# SCH_meta-RCU_2025-01-19.net
KiCad netlist of a schematic drawn in EasyEDA
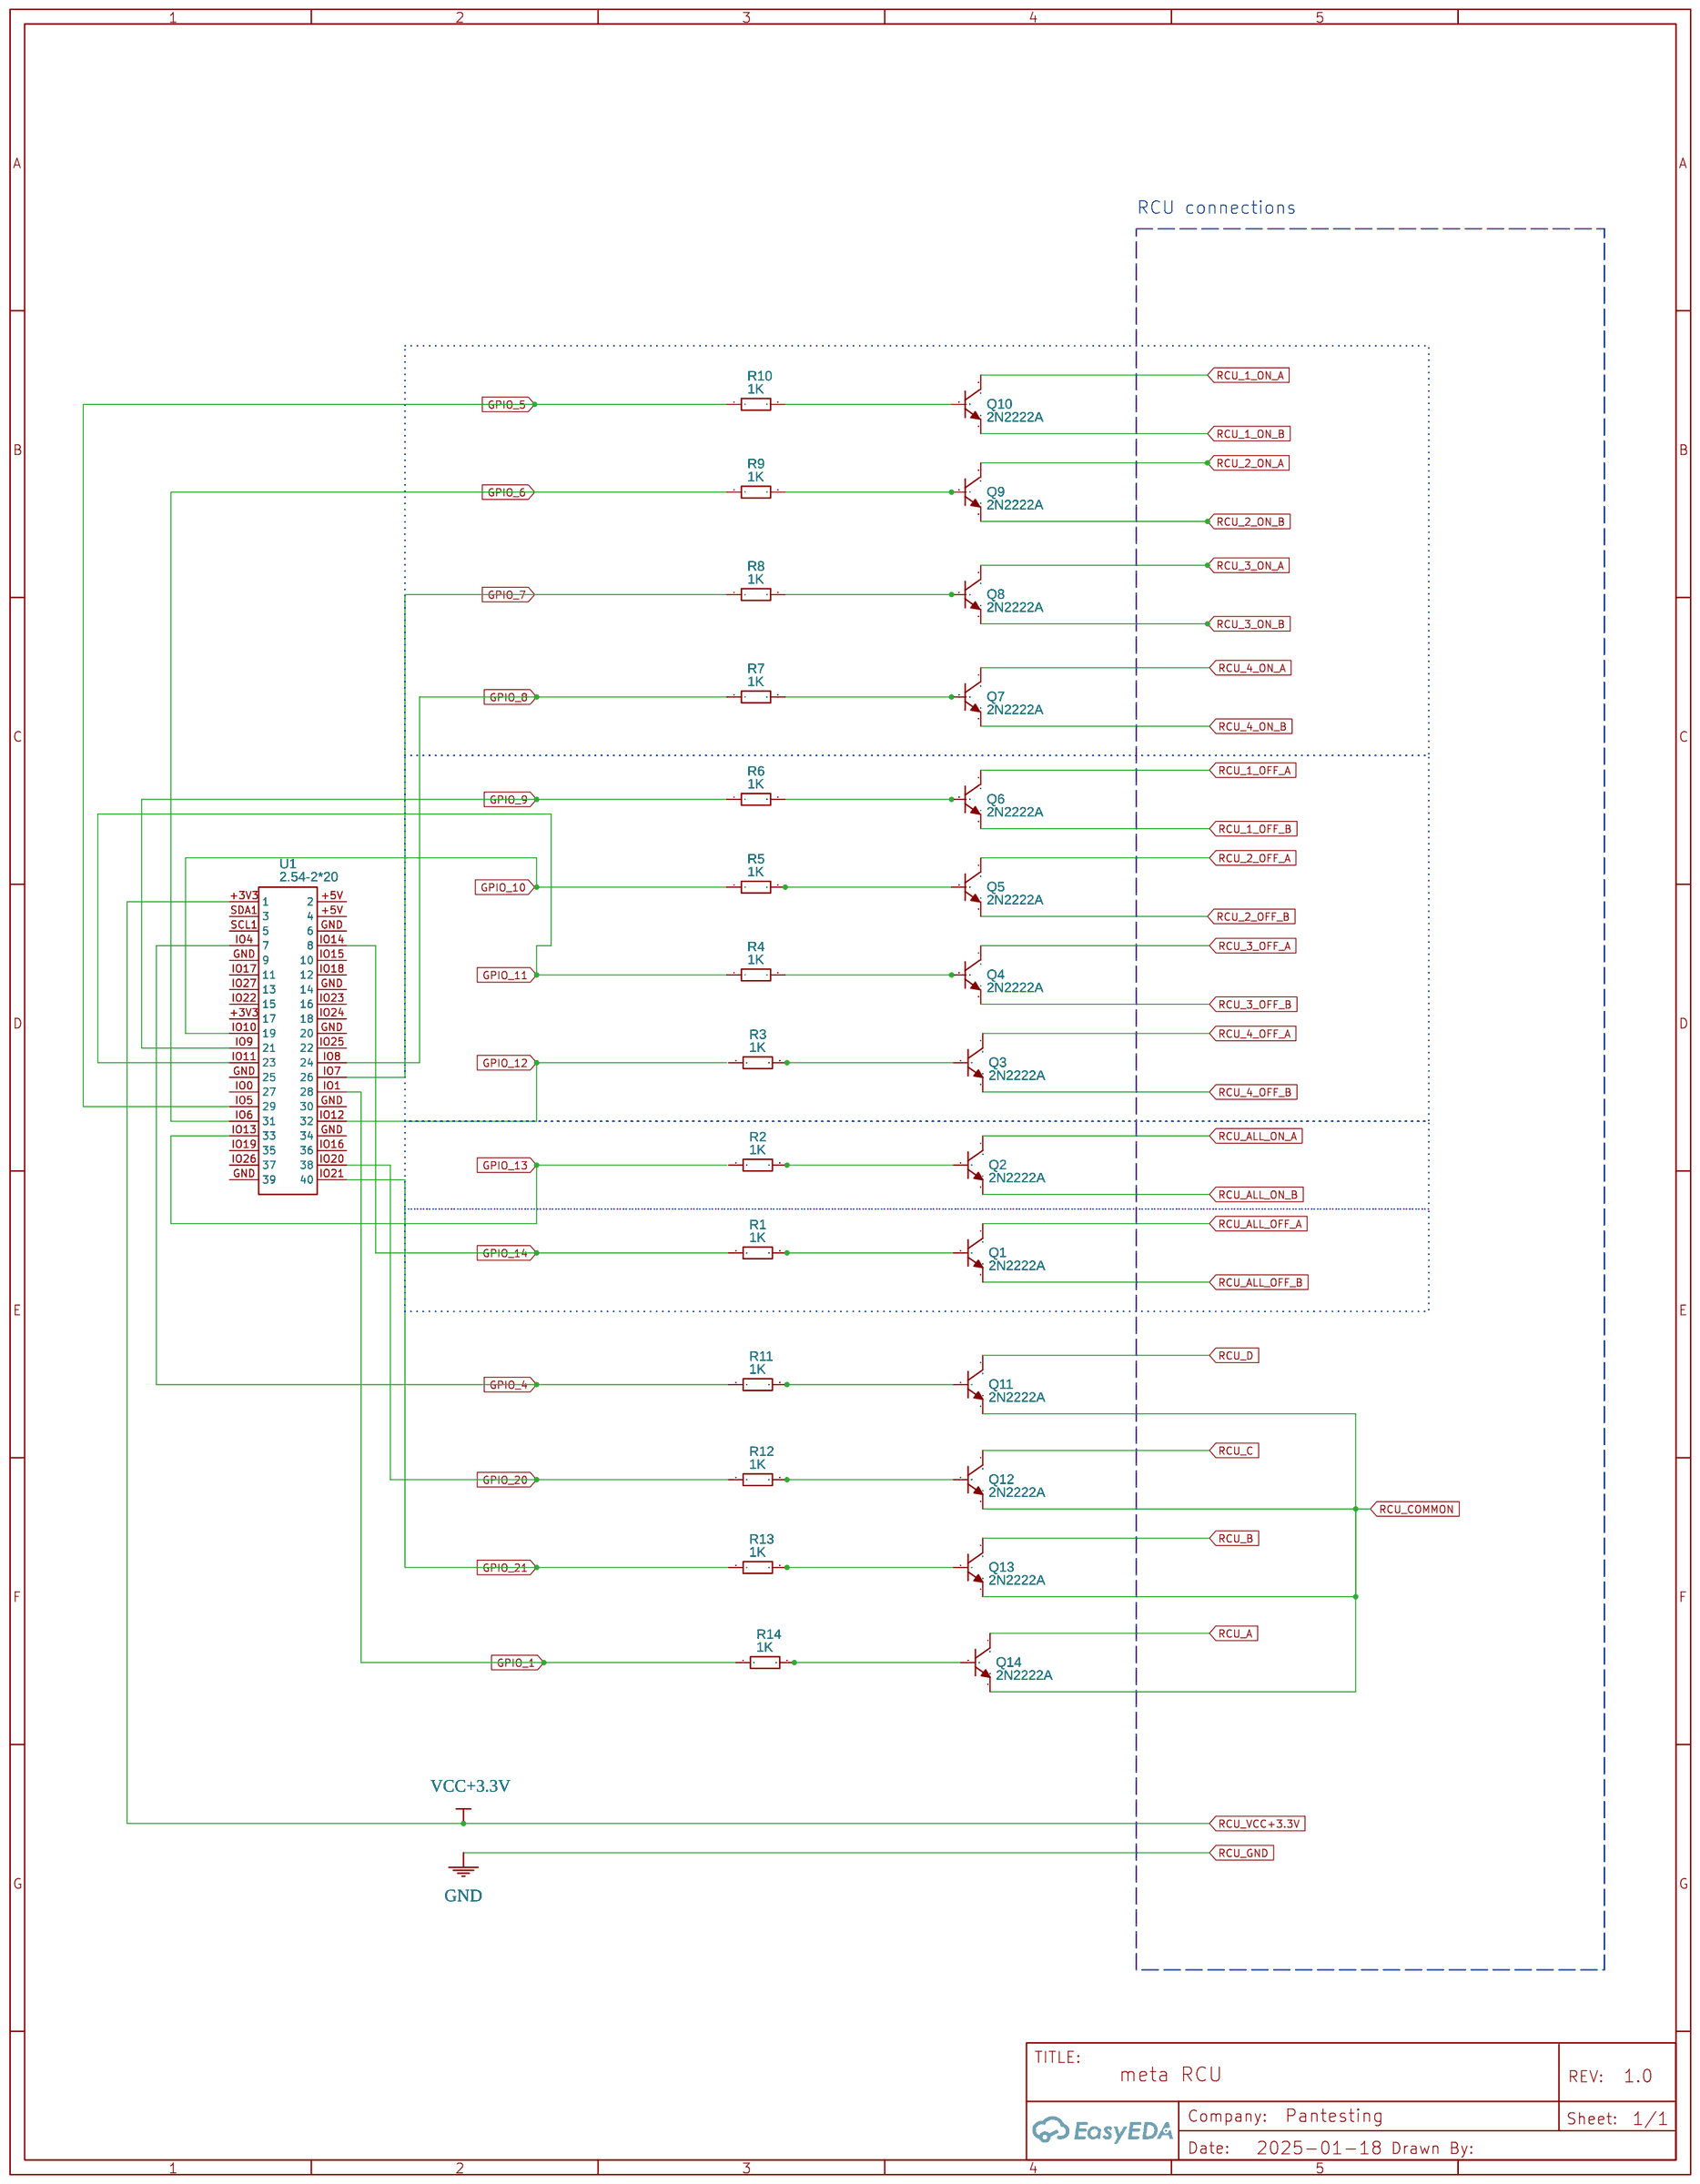
[diagram p0: meta RCU]
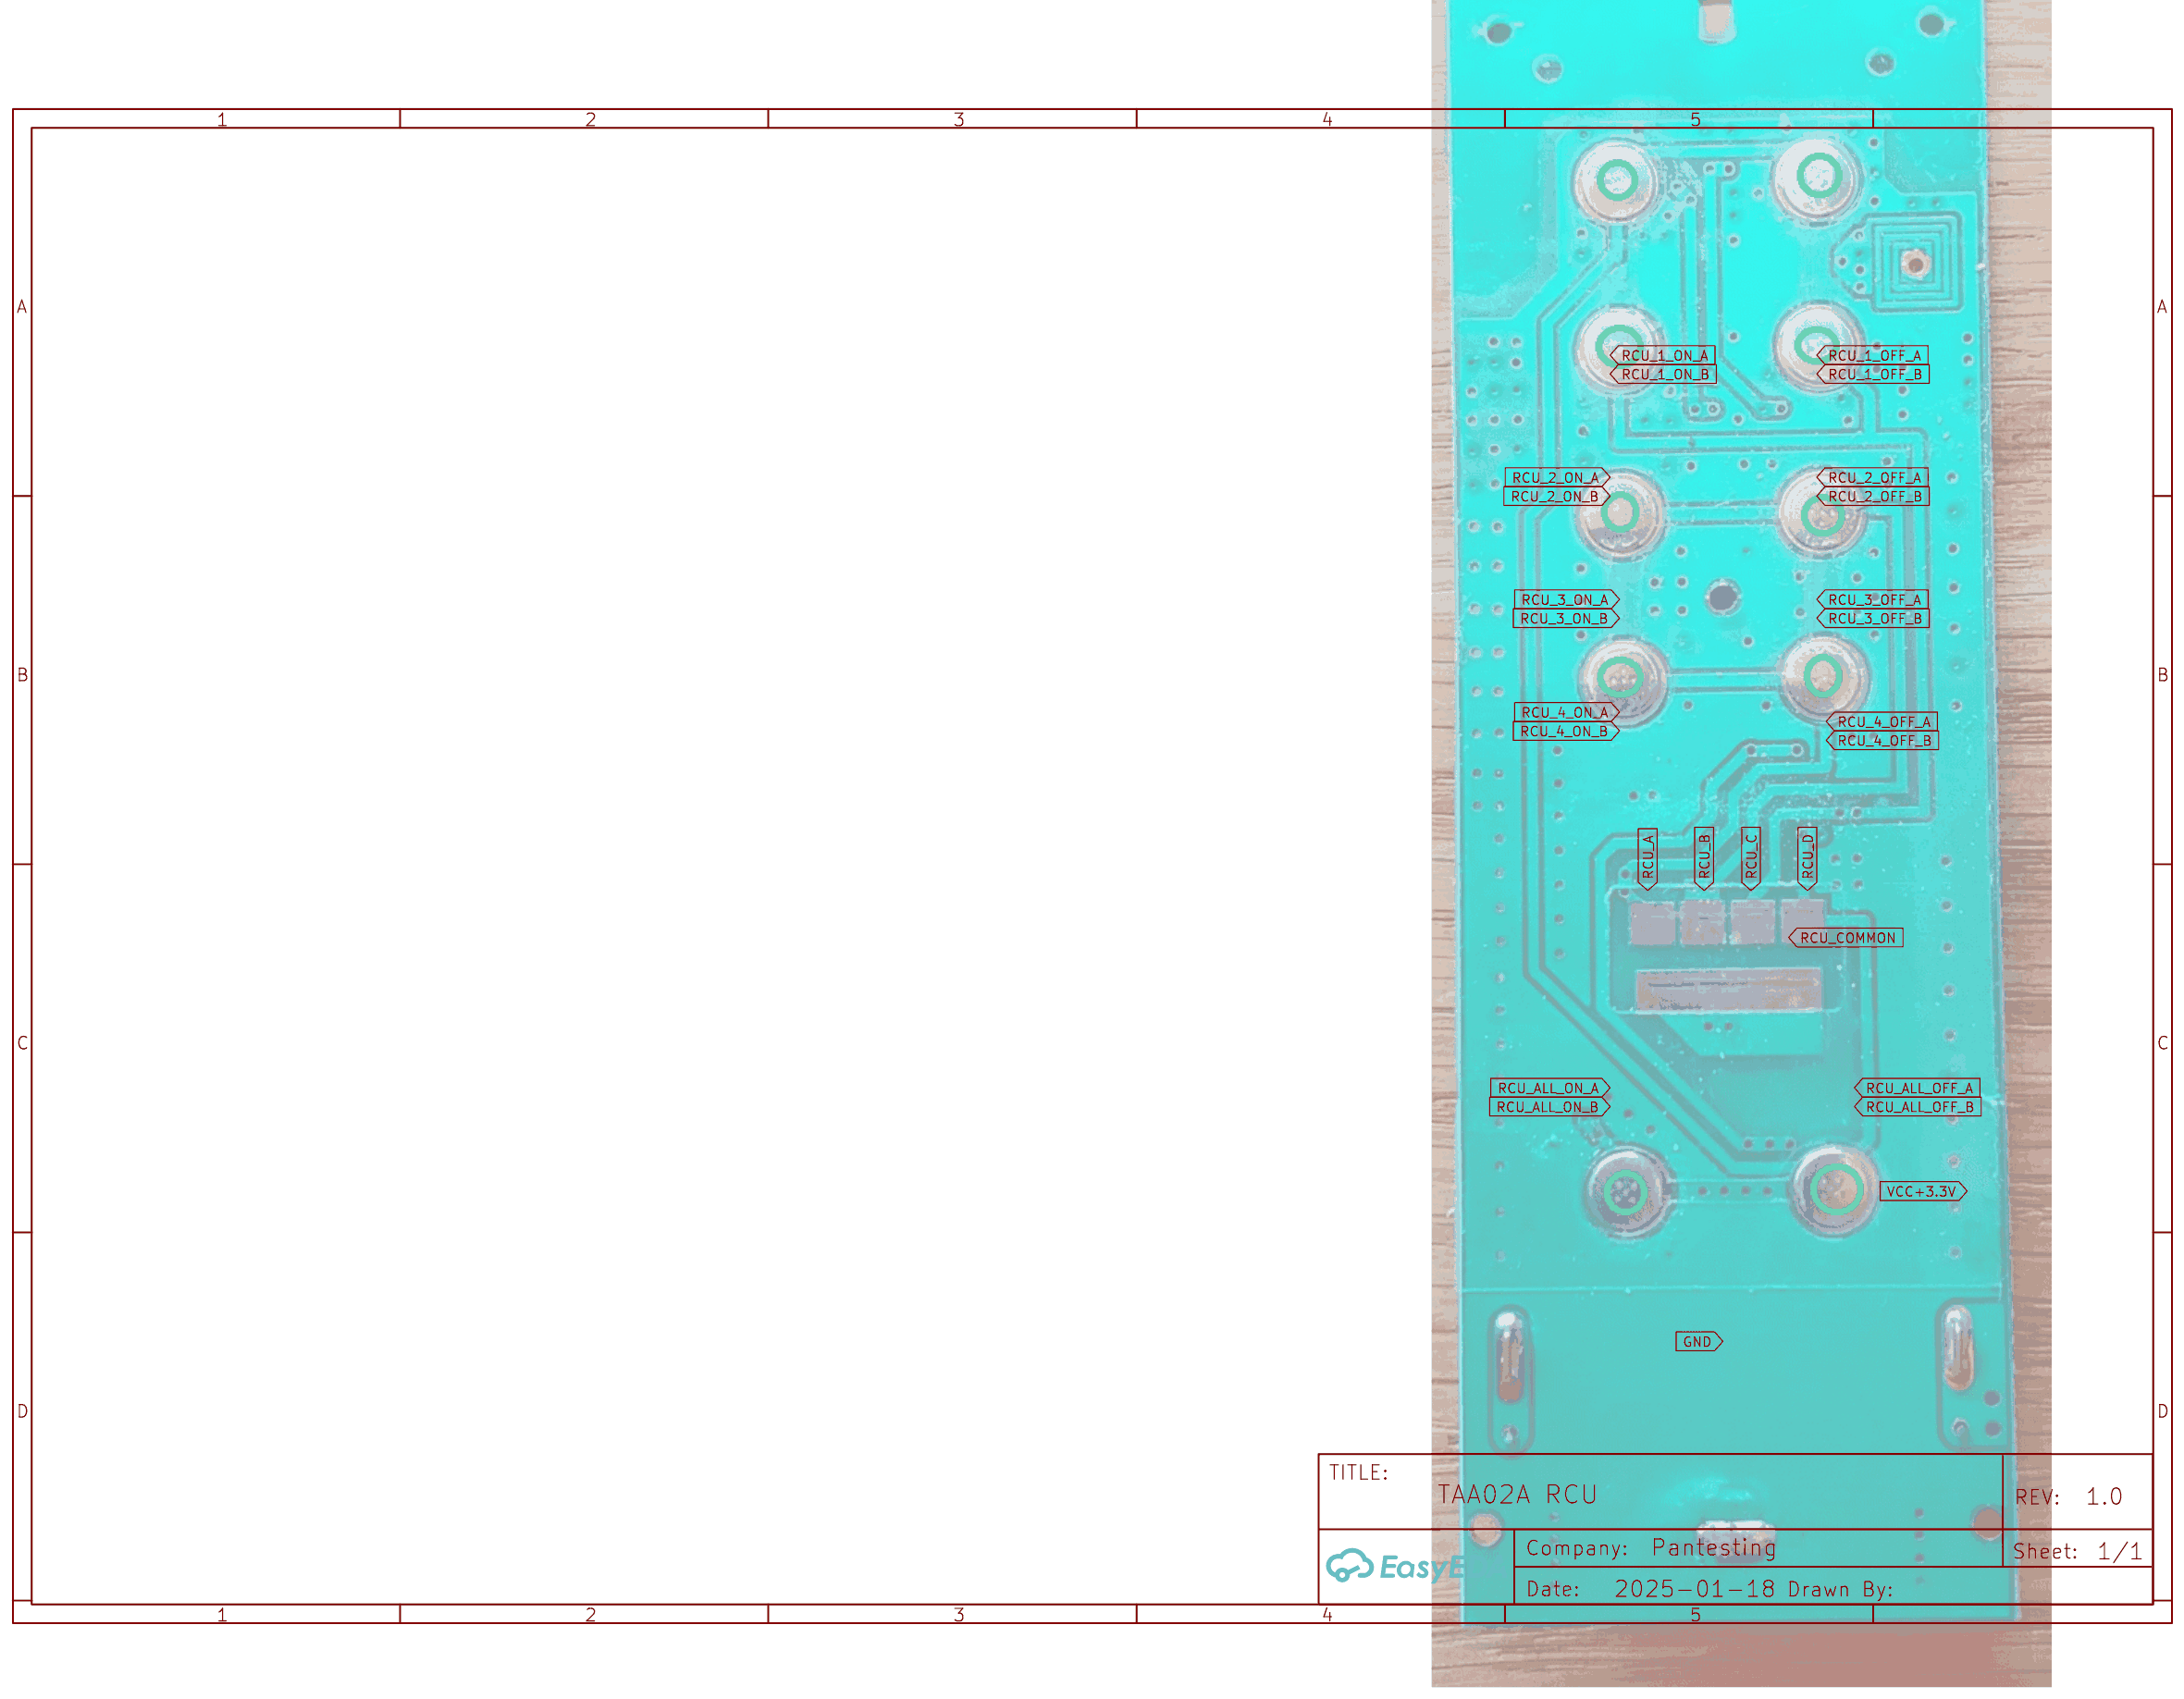
[diagram p1: TAA02A RCU]

(export (version "E")
  (design (tool "Eeschema 10.0.6"))
  (components
    (comp (ref "Q1")
      (value "2N2222A")
      (fields (field (name "Manufacturer") "BLUE ROCKET(蓝箭)"))
      (libsource (lib "") (part "2N2222A"))
    )
    (comp (ref "Q2")
      (value "2N2222A")
      (fields (field (name "Manufacturer") "BLUE ROCKET(蓝箭)"))
      (libsource (lib "") (part "2N2222A"))
    )
    (comp (ref "Q3")
      (value "2N2222A")
      (fields (field (name "Manufacturer") "BLUE ROCKET(蓝箭)"))
      (libsource (lib "") (part "2N2222A"))
    )
    (comp (ref "Q4")
      (value "2N2222A")
      (fields (field (name "Manufacturer") "BLUE ROCKET(蓝箭)"))
      (libsource (lib "") (part "2N2222A_1"))
    )
    (comp (ref "Q5")
      (value "2N2222A")
      (fields (field (name "Manufacturer") "BLUE ROCKET(蓝箭)"))
      (libsource (lib "") (part "2N2222A_1"))
    )
    (comp (ref "Q6")
      (value "2N2222A")
      (fields (field (name "Manufacturer") "BLUE ROCKET(蓝箭)"))
      (libsource (lib "") (part "2N2222A_1"))
    )
    (comp (ref "Q7")
      (value "2N2222A")
      (fields (field (name "Manufacturer") "BLUE ROCKET(蓝箭)"))
      (libsource (lib "") (part "2N2222A_1"))
    )
    (comp (ref "Q8")
      (value "2N2222A")
      (fields (field (name "Manufacturer") "BLUE ROCKET(蓝箭)"))
      (libsource (lib "") (part "2N2222A_1"))
    )
    (comp (ref "Q9")
      (value "2N2222A")
      (fields (field (name "Manufacturer") "BLUE ROCKET(蓝箭)"))
      (libsource (lib "") (part "2N2222A_1"))
    )
    (comp (ref "Q10")
      (value "2N2222A")
      (fields (field (name "Manufacturer") "BLUE ROCKET(蓝箭)"))
      (libsource (lib "") (part "2N2222A_1"))
    )
    (comp (ref "Q11")
      (value "2N2222A")
      (fields (field (name "Manufacturer") "BLUE ROCKET(蓝箭)"))
      (libsource (lib "") (part "2N2222A"))
    )
    (comp (ref "Q12")
      (value "2N2222A")
      (fields (field (name "Manufacturer") "BLUE ROCKET(蓝箭)"))
      (libsource (lib "") (part "2N2222A"))
    )
    (comp (ref "Q13")
      (value "2N2222A")
      (fields (field (name "Manufacturer") "BLUE ROCKET(蓝箭)"))
      (libsource (lib "") (part "2N2222A"))
    )
    (comp (ref "Q14")
      (value "2N2222A")
      (fields (field (name "Manufacturer") "BLUE ROCKET(蓝箭)"))
      (libsource (lib "") (part "2N2222A"))
    )
    (comp (ref "R1")
      (value "1K")
      (fields (field (name "Manufacturer Part") "CFR0W4J0102A50") (field (name "Manufacturer") "UniOhm"))
      (libsource (lib "") (part "CFR0W4J0102A50"))
    )
    (comp (ref "R2")
      (value "1K")
      (fields (field (name "Manufacturer Part") "CFR0W4J0102A50") (field (name "Manufacturer") "UniOhm"))
      (libsource (lib "") (part "CFR0W4J0102A50"))
    )
    (comp (ref "R3")
      (value "1K")
      (fields (field (name "Manufacturer Part") "CFR0W4J0102A50") (field (name "Manufacturer") "UniOhm"))
      (libsource (lib "") (part "CFR0W4J0102A50"))
    )
    (comp (ref "R4")
      (value "1K")
      (fields (field (name "Manufacturer Part") "CFR0W4J0102A50") (field (name "Manufacturer") "UniOhm"))
      (libsource (lib "") (part "CFR0W4J0102A50"))
    )
    (comp (ref "R5")
      (value "1K")
      (fields (field (name "Manufacturer Part") "CFR0W4J0102A50") (field (name "Manufacturer") "UniOhm"))
      (libsource (lib "") (part "CFR0W4J0102A50"))
    )
    (comp (ref "R6")
      (value "1K")
      (fields (field (name "Manufacturer Part") "CFR0W4J0102A50") (field (name "Manufacturer") "UniOhm"))
      (libsource (lib "") (part "CFR0W4J0102A50"))
    )
    (comp (ref "R7")
      (value "1K")
      (fields (field (name "Manufacturer Part") "CFR0W4J0102A50") (field (name "Manufacturer") "UniOhm"))
      (libsource (lib "") (part "CFR0W4J0102A50"))
    )
    (comp (ref "R8")
      (value "1K")
      (fields (field (name "Manufacturer Part") "CFR0W4J0102A50") (field (name "Manufacturer") "UniOhm"))
      (libsource (lib "") (part "CFR0W4J0102A50"))
    )
    (comp (ref "R9")
      (value "1K")
      (fields (field (name "Manufacturer Part") "CFR0W4J0102A50") (field (name "Manufacturer") "UniOhm"))
      (libsource (lib "") (part "CFR0W4J0102A50"))
    )
    (comp (ref "R10")
      (value "1K")
      (fields (field (name "Manufacturer Part") "CFR0W4J0102A50") (field (name "Manufacturer") "UniOhm"))
      (libsource (lib "") (part "CFR0W4J0102A50"))
    )
    (comp (ref "R11")
      (value "1K")
      (fields (field (name "Manufacturer Part") "CFR0W4J0102A50") (field (name "Manufacturer") "UniOhm"))
      (libsource (lib "") (part "CFR0W4J0102A50"))
    )
    (comp (ref "R12")
      (value "1K")
      (fields (field (name "Manufacturer Part") "CFR0W4J0102A50") (field (name "Manufacturer") "UniOhm"))
      (libsource (lib "") (part "CFR0W4J0102A50"))
    )
    (comp (ref "R13")
      (value "1K")
      (fields (field (name "Manufacturer Part") "CFR0W4J0102A50") (field (name "Manufacturer") "UniOhm"))
      (libsource (lib "") (part "CFR0W4J0102A50"))
    )
    (comp (ref "R14")
      (value "1K")
      (fields (field (name "Manufacturer Part") "CFR0W4J0102A50") (field (name "Manufacturer") "UniOhm"))
      (libsource (lib "") (part "CFR0W4J0102A50"))
    )
    (comp (ref "U1")
      (value "2.54-2*20")
      (fields (field (name "Manufacturer") "ZHOURI(洲日)"))
      (libsource (lib "") (part "2.54-2*20"))
    )
  )
  (nets
    (net (code "2") (name "GPIO_1") (class "Default")
      (node (ref "U1") (pin "IO1") (pinfunction "28_IO1") (pintype "unspecified"))
    )
    (net (code "3") (name "GPIO_4") (class "Default")
      (node (ref "R11") (pin "1") (pinfunction "1_1") (pintype "input"))
      (node (ref "U1") (pin "IO4") (pinfunction "7_IO4") (pintype "unspecified"))
    )
    (net (code "4") (name "GPIO_5") (class "Default")
      (node (ref "U1") (pin "IO5") (pinfunction "29_IO5") (pintype "unspecified"))
    )
    (net (code "5") (name "GPIO_6") (class "Default")
      (node (ref "U1") (pin "IO6") (pinfunction "31_IO6") (pintype "unspecified"))
    )
    (net (code "6") (name "GPIO_7") (class "Default")
      (node (ref "U1") (pin "IO7") (pinfunction "26_IO7") (pintype "unspecified"))
    )
    (net (code "7") (name "GPIO_8") (class "Default")
      (node (ref "R7") (pin "1") (pinfunction "1_1") (pintype "input"))
      (node (ref "U1") (pin "IO8") (pinfunction "24_IO8") (pintype "unspecified"))
    )
    (net (code "8") (name "GPIO_9") (class "Default")
      (node (ref "R6") (pin "1") (pinfunction "1_1") (pintype "input"))
      (node (ref "U1") (pin "IO9") (pinfunction "21_IO9") (pintype "unspecified"))
    )
    (net (code "9") (name "GPIO_10") (class "Default")
      (node (ref "R5") (pin "1") (pinfunction "1_1") (pintype "input"))
      (node (ref "U1") (pin "IO10") (pinfunction "19_IO10") (pintype "unspecified"))
    )
    (net (code "10") (name "GPIO_11") (class "Default")
      (node (ref "R4") (pin "1") (pinfunction "1_1") (pintype "input"))
      (node (ref "U1") (pin "IO11") (pinfunction "23_IO11") (pintype "unspecified"))
    )
    (net (code "11") (name "GPIO_12") (class "Default")
      (node (ref "U1") (pin "IO12") (pinfunction "32_IO12") (pintype "unspecified"))
    )
    (net (code "12") (name "GPIO_13") (class "Default")
      (node (ref "U1") (pin "IO13") (pinfunction "33_IO13") (pintype "unspecified"))
    )
    (net (code "13") (name "GPIO_14") (class "Default")
      (node (ref "U1") (pin "IO14") (pinfunction "8_IO14") (pintype "unspecified"))
    )
    (net (code "14") (name "GPIO_20") (class "Default")
      (node (ref "U1") (pin "IO20") (pinfunction "38_IO20") (pintype "unspecified"))
    )
    (net (code "15") (name "GPIO_21") (class "Default")
      (node (ref "U1") (pin "IO21") (pinfunction "40_IO21") (pintype "unspecified"))
    )
    (net (code "16") (name "Net-(Q1-B)") (class "Default")
      (node (ref "Q1") (pin "2") (pinfunction "B_2") (pintype "unspecified"))
      (node (ref "R1") (pin "2") (pinfunction "2_2") (pintype "input"))
    )
    (net (code "17") (name "Net-(Q2-B)") (class "Default")
      (node (ref "Q2") (pin "2") (pinfunction "B_2") (pintype "unspecified"))
      (node (ref "R2") (pin "2") (pinfunction "2_2") (pintype "input"))
    )
    (net (code "18") (name "Net-(Q3-B)") (class "Default")
      (node (ref "Q3") (pin "2") (pinfunction "B_2") (pintype "unspecified"))
      (node (ref "R3") (pin "2") (pinfunction "2_2") (pintype "input"))
    )
    (net (code "19") (name "Net-(Q4-B)") (class "Default")
      (node (ref "Q4") (pin "2") (pinfunction "B_2") (pintype "unspecified"))
      (node (ref "R4") (pin "2") (pinfunction "2_2") (pintype "input"))
    )
    (net (code "20") (name "Net-(Q5-B)") (class "Default")
      (node (ref "Q5") (pin "2") (pinfunction "B_2") (pintype "unspecified"))
      (node (ref "R5") (pin "2") (pinfunction "2_2") (pintype "input"))
    )
    (net (code "21") (name "Net-(Q6-B)") (class "Default")
      (node (ref "Q6") (pin "2") (pinfunction "B_2") (pintype "unspecified"))
      (node (ref "R6") (pin "2") (pinfunction "2_2") (pintype "input"))
    )
    (net (code "22") (name "Net-(Q7-B)") (class "Default")
      (node (ref "Q7") (pin "2") (pinfunction "B_2") (pintype "unspecified"))
      (node (ref "R7") (pin "2") (pinfunction "2_2") (pintype "input"))
    )
    (net (code "23") (name "Net-(Q8-B)") (class "Default")
      (node (ref "Q8") (pin "2") (pinfunction "B_2") (pintype "unspecified"))
      (node (ref "R8") (pin "2") (pinfunction "2_2") (pintype "input"))
    )
    (net (code "24") (name "Net-(Q9-B)") (class "Default")
      (node (ref "Q9") (pin "2") (pinfunction "B_2") (pintype "unspecified"))
      (node (ref "R9") (pin "2") (pinfunction "2_2") (pintype "input"))
    )
    (net (code "25") (name "Net-(Q10-B)") (class "Default")
      (node (ref "Q10") (pin "2") (pinfunction "B_2") (pintype "unspecified"))
      (node (ref "R10") (pin "2") (pinfunction "2_2") (pintype "input"))
    )
    (net (code "26") (name "Net-(Q11-B)") (class "Default")
      (node (ref "Q11") (pin "2") (pinfunction "B_2") (pintype "unspecified"))
      (node (ref "R11") (pin "2") (pinfunction "2_2") (pintype "input"))
    )
    (net (code "27") (name "Net-(Q12-B)") (class "Default")
      (node (ref "Q12") (pin "2") (pinfunction "B_2") (pintype "unspecified"))
      (node (ref "R12") (pin "2") (pinfunction "2_2") (pintype "input"))
    )
    (net (code "28") (name "Net-(Q13-B)") (class "Default")
      (node (ref "Q13") (pin "2") (pinfunction "B_2") (pintype "unspecified"))
      (node (ref "R13") (pin "2") (pinfunction "2_2") (pintype "input"))
    )
    (net (code "29") (name "Net-(Q14-B)") (class "Default")
      (node (ref "Q14") (pin "2") (pinfunction "B_2") (pintype "unspecified"))
      (node (ref "R14") (pin "2") (pinfunction "2_2") (pintype "input"))
    )
    (net (code "32") (name "RCU_1_ON_A") (class "Default")
      (node (ref "Q10") (pin "1") (pinfunction "C_1") (pintype "unspecified"))
    )
    (net (code "33") (name "RCU_1_ON_B") (class "Default")
      (node (ref "Q10") (pin "3") (pinfunction "E_3") (pintype "unspecified"))
    )
    (net (code "35") (name "RCU_2_OFF_B") (class "Default")
      (node (ref "Q5") (pin "3") (pinfunction "E_3") (pintype "unspecified"))
    )
    (net (code "41") (name "RCU_3_ON_B") (class "Default")
      (node (ref "Q8") (pin "3") (pinfunction "E_3") (pintype "unspecified"))
    )
    (net (code "42") (name "RCU_4_OFF_A") (class "Default")
      (node (ref "Q3") (pin "1") (pinfunction "C_1") (pintype "unspecified"))
    )
    (net (code "43") (name "RCU_4_OFF_B") (class "Default")
      (node (ref "Q3") (pin "3") (pinfunction "E_3") (pintype "unspecified"))
    )
    (net (code "46") (name "RCU_A") (class "Default")
      (node (ref "Q14") (pin "1") (pinfunction "C_1") (pintype "unspecified"))
    )
    (net (code "47") (name "RCU_ALL_OFF_A") (class "Default")
      (node (ref "Q1") (pin "1") (pinfunction "C_1") (pintype "unspecified"))
    )
    (net (code "48") (name "RCU_ALL_OFF_B") (class "Default")
      (node (ref "Q1") (pin "3") (pinfunction "E_3") (pintype "unspecified"))
    )
    (net (code "49") (name "RCU_ALL_ON_A") (class "Default")
      (node (ref "Q2") (pin "1") (pinfunction "C_1") (pintype "unspecified"))
    )
    (net (code "50") (name "RCU_ALL_ON_B") (class "Default")
      (node (ref "Q2") (pin "3") (pinfunction "E_3") (pintype "unspecified"))
    )
    (net (code "51") (name "RCU_B") (class "Default")
      (node (ref "Q13") (pin "1") (pinfunction "C_1") (pintype "unspecified"))
    )
    (net (code "52") (name "RCU_C") (class "Default")
      (node (ref "Q12") (pin "1") (pinfunction "C_1") (pintype "unspecified"))
    )
    (net (code "53") (name "RCU_COMMON") (class "Default")
      (node (ref "Q11") (pin "3") (pinfunction "E_3") (pintype "unspecified"))
      (node (ref "Q12") (pin "3") (pinfunction "E_3") (pintype "unspecified"))
      (node (ref "Q13") (pin "3") (pinfunction "E_3") (pintype "unspecified"))
      (node (ref "Q14") (pin "3") (pinfunction "E_3") (pintype "unspecified"))
    )
    (net (code "54") (name "RCU_D") (class "Default")
      (node (ref "Q11") (pin "1") (pinfunction "C_1") (pintype "unspecified"))
    )
    (net (code "55") (name "RCU_VCC+3.3V") (class "Default")
      (node (ref "U1") (pin "+3V3") (pinfunction "1_+3V3") (pintype "unspecified"))
    )
    (net (code "56") (name "unconnected-(Q4-C-Pad1)") (class "Default")
      (node (ref "Q4") (pin "1") (pinfunction "C_1") (pintype "unspecified"))
    )
    (net (code "57") (name "unconnected-(Q4-E-Pad3)") (class "Default")
      (node (ref "Q4") (pin "3") (pinfunction "E_3") (pintype "unspecified"))
    )
    (net (code "58") (name "unconnected-(Q5-C-Pad1)") (class "Default")
      (node (ref "Q5") (pin "1") (pinfunction "C_1") (pintype "unspecified"))
    )
    (net (code "59") (name "unconnected-(Q6-C-Pad1)") (class "Default")
      (node (ref "Q6") (pin "1") (pinfunction "C_1") (pintype "unspecified"))
    )
    (net (code "60") (name "unconnected-(Q6-E-Pad3)") (class "Default")
      (node (ref "Q6") (pin "3") (pinfunction "E_3") (pintype "unspecified"))
    )
    (net (code "61") (name "unconnected-(Q7-C-Pad1)") (class "Default")
      (node (ref "Q7") (pin "1") (pinfunction "C_1") (pintype "unspecified"))
    )
    (net (code "62") (name "unconnected-(Q7-E-Pad3)") (class "Default")
      (node (ref "Q7") (pin "3") (pinfunction "E_3") (pintype "unspecified"))
    )
    (net (code "63") (name "unconnected-(Q8-C-Pad1)") (class "Default")
      (node (ref "Q8") (pin "1") (pinfunction "C_1") (pintype "unspecified"))
    )
    (net (code "64") (name "unconnected-(Q9-C-Pad1)") (class "Default")
      (node (ref "Q9") (pin "1") (pinfunction "C_1") (pintype "unspecified"))
    )
    (net (code "65") (name "unconnected-(Q9-E-Pad3)") (class "Default")
      (node (ref "Q9") (pin "3") (pinfunction "E_3") (pintype "unspecified"))
    )
    (net (code "66") (name "unconnected-(R1-Pad1)") (class "Default")
      (node (ref "R1") (pin "1") (pinfunction "1_1") (pintype "input"))
    )
    (net (code "67") (name "unconnected-(R2-Pad1)") (class "Default")
      (node (ref "R2") (pin "1") (pinfunction "1_1") (pintype "input"))
    )
    (net (code "68") (name "unconnected-(R3-Pad1)") (class "Default")
      (node (ref "R3") (pin "1") (pinfunction "1_1") (pintype "input"))
    )
    (net (code "69") (name "unconnected-(R8-Pad1)") (class "Default")
      (node (ref "R8") (pin "1") (pinfunction "1_1") (pintype "input"))
    )
    (net (code "70") (name "unconnected-(R9-Pad1)") (class "Default")
      (node (ref "R9") (pin "1") (pinfunction "1_1") (pintype "input"))
    )
    (net (code "71") (name "unconnected-(R10-Pad1)") (class "Default")
      (node (ref "R10") (pin "1") (pinfunction "1_1") (pintype "input"))
    )
    (net (code "72") (name "unconnected-(R12-Pad1)") (class "Default")
      (node (ref "R12") (pin "1") (pinfunction "1_1") (pintype "input"))
    )
    (net (code "73") (name "unconnected-(R13-Pad1)") (class "Default")
      (node (ref "R13") (pin "1") (pinfunction "1_1") (pintype "input"))
    )
    (net (code "74") (name "unconnected-(R14-Pad1)") (class "Default")
      (node (ref "R14") (pin "1") (pinfunction "1_1") (pintype "input"))
    )
    (net (code "75") (name "unconnected-(U1-2-Pad+5V)") (class "Default")
      (node (ref "U1") (pin "+5V") (pinfunction "2_+5V") (pintype "unspecified"))
    )
    (net (code "76") (name "unconnected-(U1-3-PadSDA1)") (class "Default")
      (node (ref "U1") (pin "SDA1") (pinfunction "3_SDA1") (pintype "unspecified"))
    )
    (net (code "77") (name "unconnected-(U1-4-Pad+5V)") (class "Default")
      (node (ref "U1") (pin "+5V") (pinfunction "4_+5V") (pintype "unspecified"))
    )
    (net (code "78") (name "unconnected-(U1-5-PadSCL1)") (class "Default")
      (node (ref "U1") (pin "SCL1") (pinfunction "5_SCL1") (pintype "unspecified"))
    )
    (net (code "79") (name "unconnected-(U1-6-PadGND)") (class "Default")
      (node (ref "U1") (pin "GND") (pinfunction "6_GND") (pintype "unspecified"))
    )
    (net (code "80") (name "unconnected-(U1-9-PadGND)") (class "Default")
      (node (ref "U1") (pin "GND") (pinfunction "9_GND") (pintype "unspecified"))
    )
    (net (code "81") (name "unconnected-(U1-10-PadIO15)") (class "Default")
      (node (ref "U1") (pin "IO15") (pinfunction "10_IO15") (pintype "unspecified"))
    )
    (net (code "82") (name "unconnected-(U1-11-PadIO17)") (class "Default")
      (node (ref "U1") (pin "IO17") (pinfunction "11_IO17") (pintype "unspecified"))
    )
    (net (code "83") (name "unconnected-(U1-12-PadIO18)") (class "Default")
      (node (ref "U1") (pin "IO18") (pinfunction "12_IO18") (pintype "unspecified"))
    )
    (net (code "84") (name "unconnected-(U1-13-PadIO27)") (class "Default")
      (node (ref "U1") (pin "IO27") (pinfunction "13_IO27") (pintype "unspecified"))
    )
    (net (code "85") (name "unconnected-(U1-14-PadGND)") (class "Default")
      (node (ref "U1") (pin "GND") (pinfunction "14_GND") (pintype "unspecified"))
    )
    (net (code "86") (name "unconnected-(U1-15-PadIO22)") (class "Default")
      (node (ref "U1") (pin "IO22") (pinfunction "15_IO22") (pintype "unspecified"))
    )
    (net (code "87") (name "unconnected-(U1-16-PadIO23)") (class "Default")
      (node (ref "U1") (pin "IO23") (pinfunction "16_IO23") (pintype "unspecified"))
    )
    (net (code "88") (name "unconnected-(U1-17-Pad+3V3)") (class "Default")
      (node (ref "U1") (pin "+3V3") (pinfunction "17_+3V3") (pintype "unspecified"))
    )
    (net (code "89") (name "unconnected-(U1-18-PadIO24)") (class "Default")
      (node (ref "U1") (pin "IO24") (pinfunction "18_IO24") (pintype "unspecified"))
    )
    (net (code "90") (name "unconnected-(U1-20-PadGND)") (class "Default")
      (node (ref "U1") (pin "GND") (pinfunction "20_GND") (pintype "unspecified"))
    )
    (net (code "91") (name "unconnected-(U1-22-PadIO25)") (class "Default")
      (node (ref "U1") (pin "IO25") (pinfunction "22_IO25") (pintype "unspecified"))
    )
    (net (code "92") (name "unconnected-(U1-25-PadGND)") (class "Default")
      (node (ref "U1") (pin "GND") (pinfunction "25_GND") (pintype "unspecified"))
    )
    (net (code "93") (name "unconnected-(U1-27-PadIO0)") (class "Default")
      (node (ref "U1") (pin "IO0") (pinfunction "27_IO0") (pintype "unspecified"))
    )
    (net (code "94") (name "unconnected-(U1-30-PadGND)") (class "Default")
      (node (ref "U1") (pin "GND") (pinfunction "30_GND") (pintype "unspecified"))
    )
    (net (code "95") (name "unconnected-(U1-34-PadGND)") (class "Default")
      (node (ref "U1") (pin "GND") (pinfunction "34_GND") (pintype "unspecified"))
    )
    (net (code "96") (name "unconnected-(U1-35-PadIO19)") (class "Default")
      (node (ref "U1") (pin "IO19") (pinfunction "35_IO19") (pintype "unspecified"))
    )
    (net (code "97") (name "unconnected-(U1-36-PadIO16)") (class "Default")
      (node (ref "U1") (pin "IO16") (pinfunction "36_IO16") (pintype "unspecified"))
    )
    (net (code "98") (name "unconnected-(U1-37-PadIO26)") (class "Default")
      (node (ref "U1") (pin "IO26") (pinfunction "37_IO26") (pintype "unspecified"))
    )
    (net (code "99") (name "unconnected-(U1-39-PadGND)") (class "Default")
      (node (ref "U1") (pin "GND") (pinfunction "39_GND") (pintype "unspecified"))
    )
  )
)
